# cpu2560-double.net
KiCad netlist of a schematic drawn in Altium Designer
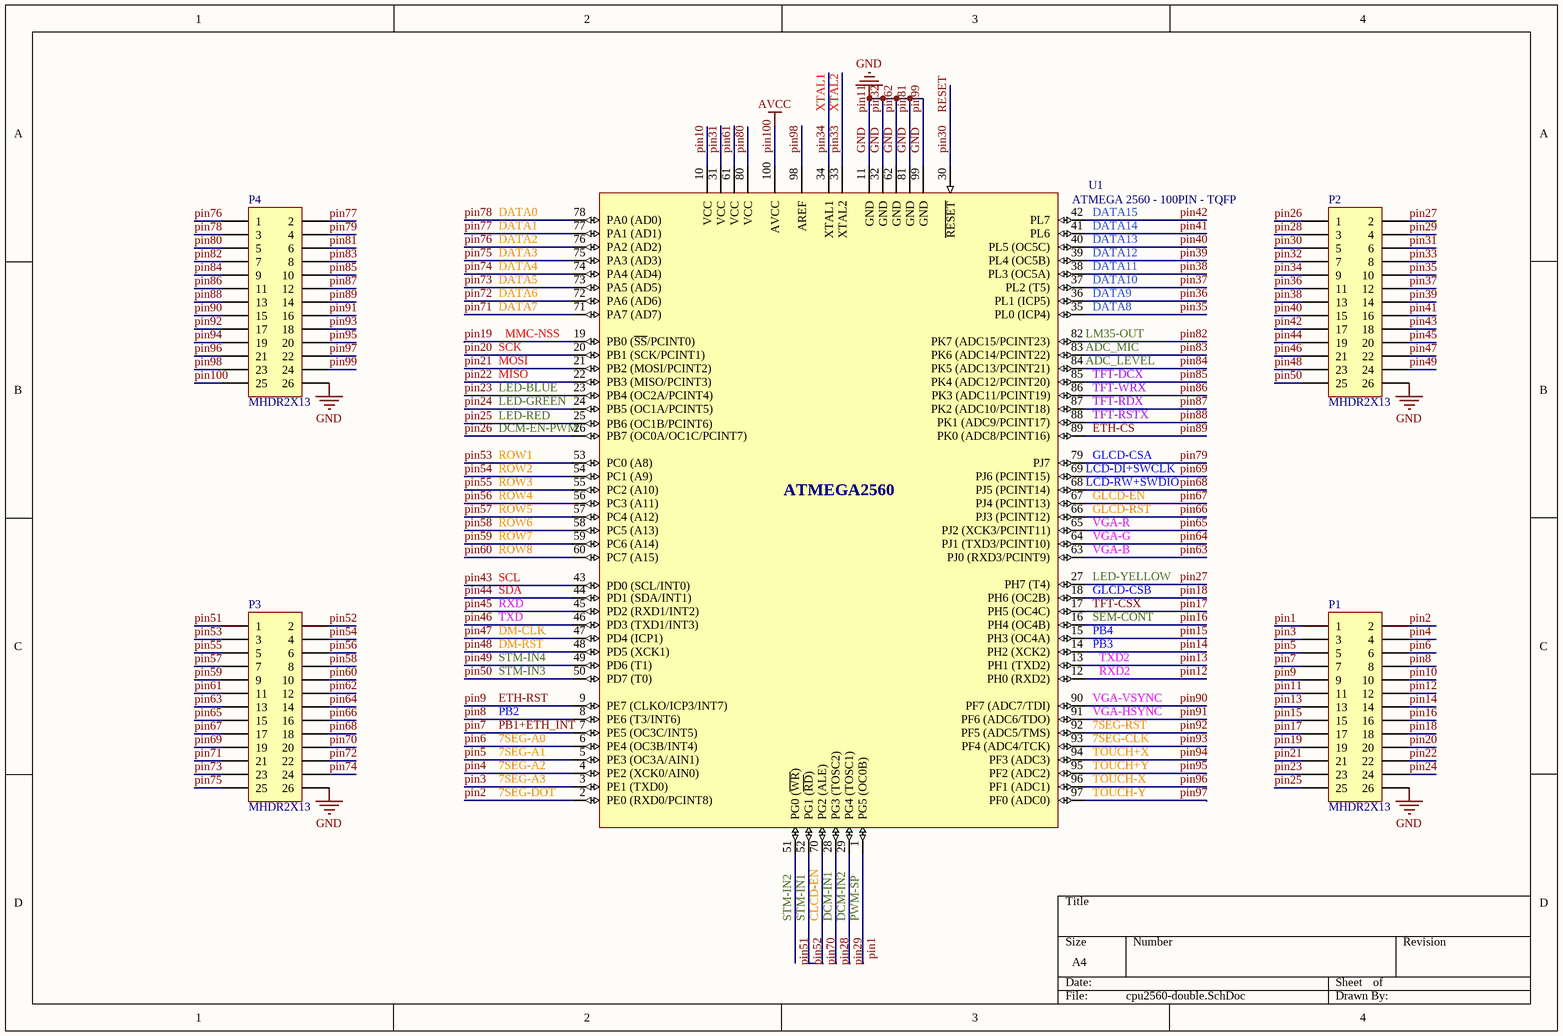
[diagram p0: cpu2560-double.SchDoc]

(export (version "E")
  (design (tool "Eeschema 10.0.6"))
  (components
    (comp (ref "P1")
      (value "MHDR2X13")
      (footprint "HED-2mm-13X2")
      (description "Header, 13-Pin, Dual row")
      (fields (field (name "PUBLISHER") "Altium Limited"))
      (libsource (lib "Miscellaneous Connectors") (part "MHDR2X13"))
    )
    (comp (ref "P2")
      (value "MHDR2X13")
      (footprint "HED-2mm-13X2")
      (description "Header, 13-Pin, Dual row")
      (fields (field (name "PUBLISHER") "Altium Limited"))
      (libsource (lib "Miscellaneous Connectors") (part "MHDR2X13"))
    )
    (comp (ref "P3")
      (value "MHDR2X13")
      (footprint "HED-2mm-13X2")
      (description "Header, 13-Pin, Dual row")
      (fields (field (name "PUBLISHER") "Altium Limited"))
      (libsource (lib "Miscellaneous Connectors") (part "MHDR2X13"))
    )
    (comp (ref "P4")
      (value "MHDR2X13")
      (footprint "HED-2mm-13X2")
      (description "Header, 13-Pin, Dual row")
      (fields (field (name "PUBLISHER") "Altium Limited"))
      (libsource (lib "Miscellaneous Connectors") (part "MHDR2X13"))
    )
    (comp (ref "U1")
      (value "ATMEGA 2560 - 100PIN - TQFP")
      (footprint "Quad100")
      (libsource (lib "Tl494") (part "ATMEGA 2560"))
    )
  )
  (nets
    (net (code "1") (name "/7SEG-A0") (class "Default")
      (node (ref "P1") (pin "6") (pinfunction "6_6") (pintype "passive"))
      (node (ref "U1") (pin "6") (pinfunction "PE4_(OC3B/INT4)_6") (pintype "bidirectional"))
    )
    (net (code "2") (name "/7SEG-A1") (class "Default")
      (node (ref "P1") (pin "5") (pinfunction "5_5") (pintype "passive"))
      (node (ref "U1") (pin "5") (pinfunction "PE3_(OC3A/AIN1)_5") (pintype "bidirectional"))
    )
    (net (code "3") (name "/7SEG-A2") (class "Default")
      (node (ref "P1") (pin "4") (pinfunction "4_4") (pintype "passive"))
      (node (ref "U1") (pin "4") (pinfunction "PE2_(XCK0/AIN0)_4") (pintype "bidirectional"))
    )
    (net (code "4") (name "/7SEG-A3") (class "Default")
      (node (ref "P1") (pin "3") (pinfunction "3_3") (pintype "passive"))
      (node (ref "U1") (pin "3") (pinfunction "PE1_(TXD0)_3") (pintype "bidirectional"))
    )
    (net (code "5") (name "/7SEG-CLK") (class "Default")
      (node (ref "P4") (pin "18") (pinfunction "18_18") (pintype "passive"))
      (node (ref "U1") (pin "93") (pinfunction "PF4_(ADC4/TCK)_93") (pintype "bidirectional"))
    )
    (net (code "6") (name "/7SEG-DOT") (class "Default")
      (node (ref "P1") (pin "2") (pinfunction "2_2") (pintype "passive"))
      (node (ref "U1") (pin "2") (pinfunction "PE0_(RXD0/PCINT8)_2") (pintype "bidirectional"))
    )
    (net (code "7") (name "/7SEG-RST") (class "Default")
      (node (ref "P4") (pin "17") (pinfunction "17_17") (pintype "passive"))
      (node (ref "U1") (pin "92") (pinfunction "PF5_(ADC5/TMS)_92") (pintype "bidirectional"))
    )
    (net (code "8") (name "/ADC_LEVEL") (class "Default")
      (node (ref "P4") (pin "9") (pinfunction "9_9") (pintype "passive"))
      (node (ref "U1") (pin "84") (pinfunction "PK5_(ADC13/PCINT21)_84") (pintype "bidirectional"))
    )
    (net (code "9") (name "/ADC_MIC") (class "Default")
      (node (ref "P4") (pin "8") (pinfunction "8_8") (pintype "passive"))
      (node (ref "U1") (pin "83") (pinfunction "PK6_(ADC14/PCINT22)_83") (pintype "bidirectional"))
    )
    (net (code "10") (name "/CLCD-EN") (class "Default")
      (node (ref "P3") (pin "20") (pinfunction "20_20") (pintype "passive"))
      (node (ref "U1") (pin "70") (pinfunction "PG2_(ALE)_70") (pintype "bidirectional"))
    )
    (net (code "11") (name "/DATA0") (class "Default")
      (node (ref "P4") (pin "3") (pinfunction "3_3") (pintype "passive"))
      (node (ref "U1") (pin "78") (pinfunction "PA0_(AD0)_78") (pintype "bidirectional"))
    )
    (net (code "12") (name "/DATA1") (class "Default")
      (node (ref "P4") (pin "2") (pinfunction "2_2") (pintype "passive"))
      (node (ref "U1") (pin "77") (pinfunction "PA1_(AD1)_77") (pintype "bidirectional"))
    )
    (net (code "13") (name "/DATA2") (class "Default")
      (node (ref "P4") (pin "1") (pinfunction "1_1") (pintype "passive"))
      (node (ref "U1") (pin "76") (pinfunction "PA2_(AD2)_76") (pintype "bidirectional"))
    )
    (net (code "14") (name "/DATA3") (class "Default")
      (node (ref "P3") (pin "25") (pinfunction "25_25") (pintype "passive"))
      (node (ref "U1") (pin "75") (pinfunction "PA3_(AD3)_75") (pintype "bidirectional"))
    )
    (net (code "15") (name "/DATA4") (class "Default")
      (node (ref "P3") (pin "24") (pinfunction "24_24") (pintype "passive"))
      (node (ref "U1") (pin "74") (pinfunction "PA4_(AD4)_74") (pintype "bidirectional"))
    )
    (net (code "16") (name "/DATA5") (class "Default")
      (node (ref "P3") (pin "23") (pinfunction "23_23") (pintype "passive"))
      (node (ref "U1") (pin "73") (pinfunction "PA5_(AD5)_73") (pintype "bidirectional"))
    )
    (net (code "17") (name "/DATA6") (class "Default")
      (node (ref "P3") (pin "22") (pinfunction "22_22") (pintype "passive"))
      (node (ref "U1") (pin "72") (pinfunction "PA6_(AD6)_72") (pintype "bidirectional"))
    )
    (net (code "18") (name "/DATA7") (class "Default")
      (node (ref "P3") (pin "21") (pinfunction "21_21") (pintype "passive"))
      (node (ref "U1") (pin "71") (pinfunction "PA7_(AD7)_71") (pintype "bidirectional"))
    )
    (net (code "19") (name "/DATA8") (class "Default")
      (node (ref "P2") (pin "10") (pinfunction "10_10") (pintype "passive"))
      (node (ref "U1") (pin "35") (pinfunction "PL0_(ICP4)_35") (pintype "bidirectional"))
    )
    (net (code "20") (name "/DATA9") (class "Default")
      (node (ref "P2") (pin "11") (pinfunction "11_11") (pintype "passive"))
      (node (ref "U1") (pin "36") (pinfunction "PL1_(ICP5)_36") (pintype "bidirectional"))
    )
    (net (code "21") (name "/DATA10") (class "Default")
      (node (ref "P2") (pin "12") (pinfunction "12_12") (pintype "passive"))
      (node (ref "U1") (pin "37") (pinfunction "PL2_(T5)_37") (pintype "bidirectional"))
    )
    (net (code "22") (name "/DATA11") (class "Default")
      (node (ref "P2") (pin "13") (pinfunction "13_13") (pintype "passive"))
      (node (ref "U1") (pin "38") (pinfunction "PL3_(OC5A)_38") (pintype "bidirectional"))
    )
    (net (code "23") (name "/DATA12") (class "Default")
      (node (ref "P2") (pin "14") (pinfunction "14_14") (pintype "passive"))
      (node (ref "U1") (pin "39") (pinfunction "PL4_(OC5B)_39") (pintype "bidirectional"))
    )
    (net (code "24") (name "/DATA13") (class "Default")
      (node (ref "P2") (pin "15") (pinfunction "15_15") (pintype "passive"))
      (node (ref "U1") (pin "40") (pinfunction "PL5_(OC5C)_40") (pintype "bidirectional"))
    )
    (net (code "25") (name "/DATA14") (class "Default")
      (node (ref "P2") (pin "16") (pinfunction "16_16") (pintype "passive"))
      (node (ref "U1") (pin "41") (pinfunction "PL6_41") (pintype "bidirectional"))
    )
    (net (code "26") (name "/DATA15") (class "Default")
      (node (ref "P2") (pin "17") (pinfunction "17_17") (pintype "passive"))
      (node (ref "U1") (pin "42") (pinfunction "PL7_42") (pintype "bidirectional"))
    )
    (net (code "27") (name "/DCM-EN-PWM") (class "Default")
      (node (ref "P2") (pin "1") (pinfunction "1_1") (pintype "passive"))
      (node (ref "U1") (pin "26") (pinfunction "PB7_(OC0A/OC1C/PCINT7)_26") (pintype "bidirectional"))
    )
    (net (code "28") (name "/DCM-IN1") (class "Default")
      (node (ref "P2") (pin "3") (pinfunction "3_3") (pintype "passive"))
      (node (ref "U1") (pin "28") (pinfunction "PG3_(TOSC2)_28") (pintype "bidirectional"))
    )
    (net (code "29") (name "/DCM-IN2") (class "Default")
      (node (ref "P2") (pin "4") (pinfunction "4_4") (pintype "passive"))
      (node (ref "U1") (pin "29") (pinfunction "PG4_(TOSC1)_29") (pintype "bidirectional"))
    )
    (net (code "30") (name "/DM-CLK") (class "Default")
      (node (ref "P2") (pin "22") (pinfunction "22_22") (pintype "passive"))
      (node (ref "U1") (pin "47") (pinfunction "PD4_(ICP1)_47") (pintype "bidirectional"))
    )
    (net (code "31") (name "/DM-RST") (class "Default")
      (node (ref "P2") (pin "23") (pinfunction "23_23") (pintype "passive"))
      (node (ref "U1") (pin "48") (pinfunction "PD5_(XCK1)_48") (pintype "bidirectional"))
    )
    (net (code "32") (name "/ETH-CS") (class "Default")
      (node (ref "P4") (pin "14") (pinfunction "14_14") (pintype "passive"))
      (node (ref "U1") (pin "89") (pinfunction "PK0_(ADC8/PCINT16)_89") (pintype "bidirectional"))
    )
    (net (code "33") (name "/ETH-RST") (class "Default")
      (node (ref "P1") (pin "9") (pinfunction "9_9") (pintype "passive"))
      (node (ref "U1") (pin "9") (pinfunction "PE7_(CLKO/ICP3/INT7)_9") (pintype "bidirectional"))
    )
    (net (code "34") (name "/GLCD-CSA") (class "Default")
      (node (ref "P4") (pin "4") (pinfunction "4_4") (pintype "passive"))
      (node (ref "U1") (pin "79") (pinfunction "PJ7_79") (pintype "bidirectional"))
    )
    (net (code "35") (name "/GLCD-CSB") (class "Default")
      (node (ref "P1") (pin "18") (pinfunction "18_18") (pintype "passive"))
      (node (ref "U1") (pin "18") (pinfunction "PH6_(OC2B)_18") (pintype "bidirectional"))
    )
    (net (code "36") (name "/GLCD-EN") (class "Default")
      (node (ref "P3") (pin "17") (pinfunction "17_17") (pintype "passive"))
      (node (ref "U1") (pin "67") (pinfunction "PJ4_(PCINT13)_67") (pintype "bidirectional"))
    )
    (net (code "37") (name "/GLCD-RST") (class "Default")
      (node (ref "P3") (pin "16") (pinfunction "16_16") (pintype "passive"))
      (node (ref "U1") (pin "66") (pinfunction "PJ3_(PCINT12)_66") (pintype "bidirectional"))
    )
    (net (code "38") (name "/LCD-DI+SWCLK") (class "Default")
      (node (ref "P3") (pin "19") (pinfunction "19_19") (pintype "passive"))
      (node (ref "U1") (pin "69") (pinfunction "PJ6_(PCINT15)_69") (pintype "bidirectional"))
    )
    (net (code "39") (name "/LCD-RW+SWDIO") (class "Default")
      (node (ref "P3") (pin "18") (pinfunction "18_18") (pintype "passive"))
      (node (ref "U1") (pin "68") (pinfunction "PJ5_(PCINT14)_68") (pintype "bidirectional"))
    )
    (net (code "40") (name "/LED-BLUE") (class "Default")
      (node (ref "P1") (pin "23") (pinfunction "23_23") (pintype "passive"))
      (node (ref "U1") (pin "23") (pinfunction "PB4_(OC2A/PCINT4)_23") (pintype "bidirectional"))
    )
    (net (code "41") (name "/LED-GREEN") (class "Default")
      (node (ref "P1") (pin "24") (pinfunction "24_24") (pintype "passive"))
      (node (ref "U1") (pin "24") (pinfunction "PB5_(OC1A/PCINT5)_24") (pintype "bidirectional"))
    )
    (net (code "42") (name "/LED-RED") (class "Default")
      (node (ref "P1") (pin "25") (pinfunction "25_25") (pintype "passive"))
      (node (ref "U1") (pin "25") (pinfunction "PB6_(OC1B/PCINT6)_25") (pintype "bidirectional"))
    )
    (net (code "43") (name "/LED-YELLOW") (class "Default")
      (node (ref "P2") (pin "2") (pinfunction "2_2") (pintype "passive"))
      (node (ref "U1") (pin "27") (pinfunction "PH7_(T4)_27") (pintype "bidirectional"))
    )
    (net (code "44") (name "/LM35-OUT") (class "Default")
      (node (ref "P4") (pin "7") (pinfunction "7_7") (pintype "passive"))
      (node (ref "U1") (pin "82") (pinfunction "PK7_(ADC15/PCINT23)_82") (pintype "bidirectional"))
    )
    (net (code "45") (name "/MISO") (class "Default")
      (node (ref "P1") (pin "22") (pinfunction "22_22") (pintype "passive"))
      (node (ref "U1") (pin "22") (pinfunction "PB3_(MISO/PCINT3)_22") (pintype "bidirectional"))
    )
    (net (code "46") (name "/MMC-NSS") (class "Default")
      (node (ref "P1") (pin "19") (pinfunction "19_19") (pintype "passive"))
      (node (ref "U1") (pin "19") (pinfunction "PB0_(~{SS}/PCINT0)_19") (pintype "bidirectional"))
    )
    (net (code "47") (name "/MOSI") (class "Default")
      (node (ref "P1") (pin "21") (pinfunction "21_21") (pintype "passive"))
      (node (ref "U1") (pin "21") (pinfunction "PB2_(MOSI/PCINT2)_21") (pintype "bidirectional"))
    )
    (net (code "48") (name "/PB1+ETH_INT") (class "Default")
      (node (ref "P1") (pin "7") (pinfunction "7_7") (pintype "passive"))
      (node (ref "U1") (pin "7") (pinfunction "PE5_(OC3C/INT5)_7") (pintype "bidirectional"))
    )
    (net (code "49") (name "/PB2") (class "Default")
      (node (ref "P1") (pin "8") (pinfunction "8_8") (pintype "passive"))
      (node (ref "U1") (pin "8") (pinfunction "PE6_(T3/INT6)_8") (pintype "bidirectional"))
    )
    (net (code "50") (name "/PB3") (class "Default")
      (node (ref "P1") (pin "14") (pinfunction "14_14") (pintype "passive"))
      (node (ref "U1") (pin "14") (pinfunction "PH2_(XCK2)_14") (pintype "bidirectional"))
    )
    (net (code "51") (name "/PB4") (class "Default")
      (node (ref "P1") (pin "15") (pinfunction "15_15") (pintype "passive"))
      (node (ref "U1") (pin "15") (pinfunction "PH3_(OC4A)_15") (pintype "bidirectional"))
    )
    (net (code "52") (name "/PWM-SP") (class "Default")
      (node (ref "P1") (pin "1") (pinfunction "1_1") (pintype "passive"))
      (node (ref "U1") (pin "1") (pinfunction "PG5_(OC0B)_1") (pintype "bidirectional"))
    )
    (net (code "53") (name "/RESET") (class "Default")
      (node (ref "P2") (pin "5") (pinfunction "5_5") (pintype "passive"))
      (node (ref "U1") (pin "30") (pinfunction "~{RESET}_30") (pintype "input"))
    )
    (net (code "54") (name "/ROW1") (class "Default")
      (node (ref "P3") (pin "3") (pinfunction "3_3") (pintype "passive"))
      (node (ref "U1") (pin "53") (pinfunction "PC0_(A8)_53") (pintype "bidirectional"))
    )
    (net (code "55") (name "/ROW2") (class "Default")
      (node (ref "P3") (pin "4") (pinfunction "4_4") (pintype "passive"))
      (node (ref "U1") (pin "54") (pinfunction "PC1_(A9)_54") (pintype "bidirectional"))
    )
    (net (code "56") (name "/ROW3") (class "Default")
      (node (ref "P3") (pin "5") (pinfunction "5_5") (pintype "passive"))
      (node (ref "U1") (pin "55") (pinfunction "PC2_(A10)_55") (pintype "bidirectional"))
    )
    (net (code "57") (name "/ROW4") (class "Default")
      (node (ref "P3") (pin "6") (pinfunction "6_6") (pintype "passive"))
      (node (ref "U1") (pin "56") (pinfunction "PC3_(A11)_56") (pintype "bidirectional"))
    )
    (net (code "58") (name "/ROW5") (class "Default")
      (node (ref "P3") (pin "7") (pinfunction "7_7") (pintype "passive"))
      (node (ref "U1") (pin "57") (pinfunction "PC4_(A12)_57") (pintype "bidirectional"))
    )
    (net (code "59") (name "/ROW6") (class "Default")
      (node (ref "P3") (pin "8") (pinfunction "8_8") (pintype "passive"))
      (node (ref "U1") (pin "58") (pinfunction "PC5_(A13)_58") (pintype "bidirectional"))
    )
    (net (code "60") (name "/ROW7") (class "Default")
      (node (ref "P3") (pin "9") (pinfunction "9_9") (pintype "passive"))
      (node (ref "U1") (pin "59") (pinfunction "PC6_(A14)_59") (pintype "bidirectional"))
    )
    (net (code "61") (name "/ROW8") (class "Default")
      (node (ref "P3") (pin "10") (pinfunction "10_10") (pintype "passive"))
      (node (ref "U1") (pin "60") (pinfunction "PC7_(A15)_60") (pintype "bidirectional"))
    )
    (net (code "62") (name "/RXD") (class "Default")
      (node (ref "P2") (pin "20") (pinfunction "20_20") (pintype "passive"))
      (node (ref "U1") (pin "45") (pinfunction "PD2_(RXD1/INT2)_45") (pintype "bidirectional"))
    )
    (net (code "63") (name "/RXD2") (class "Default")
      (node (ref "P1") (pin "12") (pinfunction "12_12") (pintype "passive"))
      (node (ref "U1") (pin "12") (pinfunction "PH0_(RXD2)_12") (pintype "bidirectional"))
    )
    (net (code "64") (name "/SCK") (class "Default")
      (node (ref "P1") (pin "20") (pinfunction "20_20") (pintype "passive"))
      (node (ref "U1") (pin "20") (pinfunction "PB1_(SCK/PCINT1)_20") (pintype "bidirectional"))
    )
    (net (code "65") (name "/SCL") (class "Default")
      (node (ref "P2") (pin "18") (pinfunction "18_18") (pintype "passive"))
      (node (ref "U1") (pin "43") (pinfunction "PD0_(SCL/INT0)_43") (pintype "bidirectional"))
    )
    (net (code "66") (name "/SDA") (class "Default")
      (node (ref "P2") (pin "19") (pinfunction "19_19") (pintype "passive"))
      (node (ref "U1") (pin "44") (pinfunction "PD1_(SDA/INT1)_44") (pintype "bidirectional"))
    )
    (net (code "67") (name "/SEM-CONT") (class "Default")
      (node (ref "P1") (pin "16") (pinfunction "16_16") (pintype "passive"))
      (node (ref "U1") (pin "16") (pinfunction "PH4_(OC4B)_16") (pintype "bidirectional"))
    )
    (net (code "68") (name "/STM-IN1") (class "Default")
      (node (ref "P3") (pin "2") (pinfunction "2_2") (pintype "passive"))
      (node (ref "U1") (pin "52") (pinfunction "PG1_(~{RD})_52") (pintype "bidirectional"))
    )
    (net (code "69") (name "/STM-IN2") (class "Default")
      (node (ref "P3") (pin "1") (pinfunction "1_1") (pintype "passive"))
      (node (ref "U1") (pin "51") (pinfunction "PG0_(~{WR})_51") (pintype "bidirectional"))
    )
    (net (code "70") (name "/STM-IN3") (class "Default")
      (node (ref "P2") (pin "25") (pinfunction "25_25") (pintype "passive"))
      (node (ref "U1") (pin "50") (pinfunction "PD7_(T0)_50") (pintype "bidirectional"))
    )
    (net (code "71") (name "/STM-IN4") (class "Default")
      (node (ref "P2") (pin "24") (pinfunction "24_24") (pintype "passive"))
      (node (ref "U1") (pin "49") (pinfunction "PD6_(T1)_49") (pintype "bidirectional"))
    )
    (net (code "72") (name "/TFT-CSX") (class "Default")
      (node (ref "P1") (pin "17") (pinfunction "17_17") (pintype "passive"))
      (node (ref "U1") (pin "17") (pinfunction "PH5_(OC4C)_17") (pintype "bidirectional"))
    )
    (net (code "73") (name "/TFT-DCX") (class "Default")
      (node (ref "P4") (pin "10") (pinfunction "10_10") (pintype "passive"))
      (node (ref "U1") (pin "85") (pinfunction "PK4_(ADC12/PCINT20)_85") (pintype "bidirectional"))
    )
    (net (code "74") (name "/TFT-RDX") (class "Default")
      (node (ref "P4") (pin "12") (pinfunction "12_12") (pintype "passive"))
      (node (ref "U1") (pin "87") (pinfunction "PK2_(ADC10/PCINT18)_87") (pintype "bidirectional"))
    )
    (net (code "75") (name "/TFT-RSTX") (class "Default")
      (node (ref "P4") (pin "13") (pinfunction "13_13") (pintype "passive"))
      (node (ref "U1") (pin "88") (pinfunction "PK1_(ADC9/PCINT17)_88") (pintype "bidirectional"))
    )
    (net (code "76") (name "/TFT-WRX") (class "Default")
      (node (ref "P4") (pin "11") (pinfunction "11_11") (pintype "passive"))
      (node (ref "U1") (pin "86") (pinfunction "PK3_(ADC11/PCINT19)_86") (pintype "bidirectional"))
    )
    (net (code "77") (name "/TOUCH+X") (class "Default")
      (node (ref "P4") (pin "19") (pinfunction "19_19") (pintype "passive"))
      (node (ref "U1") (pin "94") (pinfunction "PF3_(ADC3)_94") (pintype "bidirectional"))
    )
    (net (code "78") (name "/TOUCH+Y") (class "Default")
      (node (ref "P4") (pin "20") (pinfunction "20_20") (pintype "passive"))
      (node (ref "U1") (pin "95") (pinfunction "PF2_(ADC2)_95") (pintype "bidirectional"))
    )
    (net (code "79") (name "/TOUCH-X") (class "Default")
      (node (ref "P4") (pin "21") (pinfunction "21_21") (pintype "passive"))
      (node (ref "U1") (pin "96") (pinfunction "PF1_(ADC1)_96") (pintype "bidirectional"))
    )
    (net (code "80") (name "/TOUCH-Y") (class "Default")
      (node (ref "P4") (pin "22") (pinfunction "22_22") (pintype "passive"))
      (node (ref "U1") (pin "97") (pinfunction "PF0_(ADC0)_97") (pintype "bidirectional"))
    )
    (net (code "81") (name "/TXD") (class "Default")
      (node (ref "P2") (pin "21") (pinfunction "21_21") (pintype "passive"))
      (node (ref "U1") (pin "46") (pinfunction "PD3_(TXD1/INT3)_46") (pintype "bidirectional"))
    )
    (net (code "82") (name "/TXD2") (class "Default")
      (node (ref "P1") (pin "13") (pinfunction "13_13") (pintype "passive"))
      (node (ref "U1") (pin "13") (pinfunction "PH1_(TXD2)_13") (pintype "bidirectional"))
    )
    (net (code "83") (name "/VGA-B") (class "Default")
      (node (ref "P3") (pin "13") (pinfunction "13_13") (pintype "passive"))
      (node (ref "U1") (pin "63") (pinfunction "PJ0_(RXD3/PCINT9)_63") (pintype "bidirectional"))
    )
    (net (code "84") (name "/VGA-G") (class "Default")
      (node (ref "P3") (pin "14") (pinfunction "14_14") (pintype "passive"))
      (node (ref "U1") (pin "64") (pinfunction "PJ1_(TXD3/PCINT10)_64") (pintype "bidirectional"))
    )
    (net (code "85") (name "/VGA-HSYNC") (class "Default")
      (node (ref "P4") (pin "16") (pinfunction "16_16") (pintype "passive"))
      (node (ref "U1") (pin "91") (pinfunction "PF6_(ADC6/TDO)_91") (pintype "bidirectional"))
    )
    (net (code "86") (name "/VGA-R") (class "Default")
      (node (ref "P3") (pin "15") (pinfunction "15_15") (pintype "passive"))
      (node (ref "U1") (pin "65") (pinfunction "PJ2_(XCK3/PCINT11)_65") (pintype "bidirectional"))
    )
    (net (code "87") (name "/VGA-VSYNC") (class "Default")
      (node (ref "P4") (pin "15") (pinfunction "15_15") (pintype "passive"))
      (node (ref "U1") (pin "90") (pinfunction "PF7_(ADC7/TDI)_90") (pintype "bidirectional"))
    )
    (net (code "88") (name "/XTAL1") (class "Default")
      (node (ref "P2") (pin "9") (pinfunction "9_9") (pintype "passive"))
      (node (ref "U1") (pin "34") (pinfunction "XTAL1_34") (pintype "passive"))
    )
    (net (code "89") (name "/XTAL2") (class "Default")
      (node (ref "P2") (pin "8") (pinfunction "8_8") (pintype "passive"))
      (node (ref "U1") (pin "33") (pinfunction "XTAL2_33") (pintype "passive"))
    )
    (net (code "90") (name "/pin10") (class "Default")
      (node (ref "P1") (pin "10") (pinfunction "10_10") (pintype "passive"))
      (node (ref "U1") (pin "10") (pinfunction "VCC_10") (pintype "power_in"))
    )
    (net (code "91") (name "/pin31") (class "Default")
      (node (ref "P2") (pin "6") (pinfunction "6_6") (pintype "passive"))
      (node (ref "U1") (pin "31") (pinfunction "VCC_31") (pintype "power_in"))
    )
    (net (code "92") (name "/pin61") (class "Default")
      (node (ref "P3") (pin "11") (pinfunction "11_11") (pintype "passive"))
      (node (ref "U1") (pin "61") (pinfunction "VCC_61") (pintype "power_in"))
    )
    (net (code "93") (name "/pin80") (class "Default")
      (node (ref "P4") (pin "5") (pinfunction "5_5") (pintype "passive"))
      (node (ref "U1") (pin "80") (pinfunction "VCC_80") (pintype "power_in"))
    )
    (net (code "94") (name "/pin98") (class "Default")
      (node (ref "P4") (pin "23") (pinfunction "23_23") (pintype "passive"))
      (node (ref "U1") (pin "98") (pinfunction "AREF_98") (pintype "power_in"))
    )
    (net (code "95") (name "AVCC") (class "Default")
      (node (ref "P4") (pin "25") (pinfunction "25_25") (pintype "passive"))
      (node (ref "U1") (pin "100") (pinfunction "AVCC_100") (pintype "power_in"))
    )
    (net (code "96") (name "GND") (class "Default")
      (node (ref "P1") (pin "11") (pinfunction "11_11") (pintype "passive"))
      (node (ref "P1") (pin "26") (pinfunction "26_26") (pintype "passive"))
      (node (ref "P2") (pin "26") (pinfunction "26_26") (pintype "passive"))
      (node (ref "P2") (pin "7") (pinfunction "7_7") (pintype "passive"))
      (node (ref "P3") (pin "12") (pinfunction "12_12") (pintype "passive"))
      (node (ref "P3") (pin "26") (pinfunction "26_26") (pintype "passive"))
      (node (ref "P4") (pin "24") (pinfunction "24_24") (pintype "passive"))
      (node (ref "P4") (pin "26") (pinfunction "26_26") (pintype "passive"))
      (node (ref "P4") (pin "6") (pinfunction "6_6") (pintype "passive"))
      (node (ref "U1") (pin "11") (pinfunction "GND_11") (pintype "power_in"))
      (node (ref "U1") (pin "32") (pinfunction "GND_32") (pintype "power_in"))
      (node (ref "U1") (pin "62") (pinfunction "GND_62") (pintype "power_in"))
      (node (ref "U1") (pin "81") (pinfunction "GND_81") (pintype "power_in"))
      (node (ref "U1") (pin "99") (pinfunction "GND_99") (pintype "power_in"))
    )
  )
)
